# stm32hw02.net
KiCad netlist of a schematic drawn in EAGLE
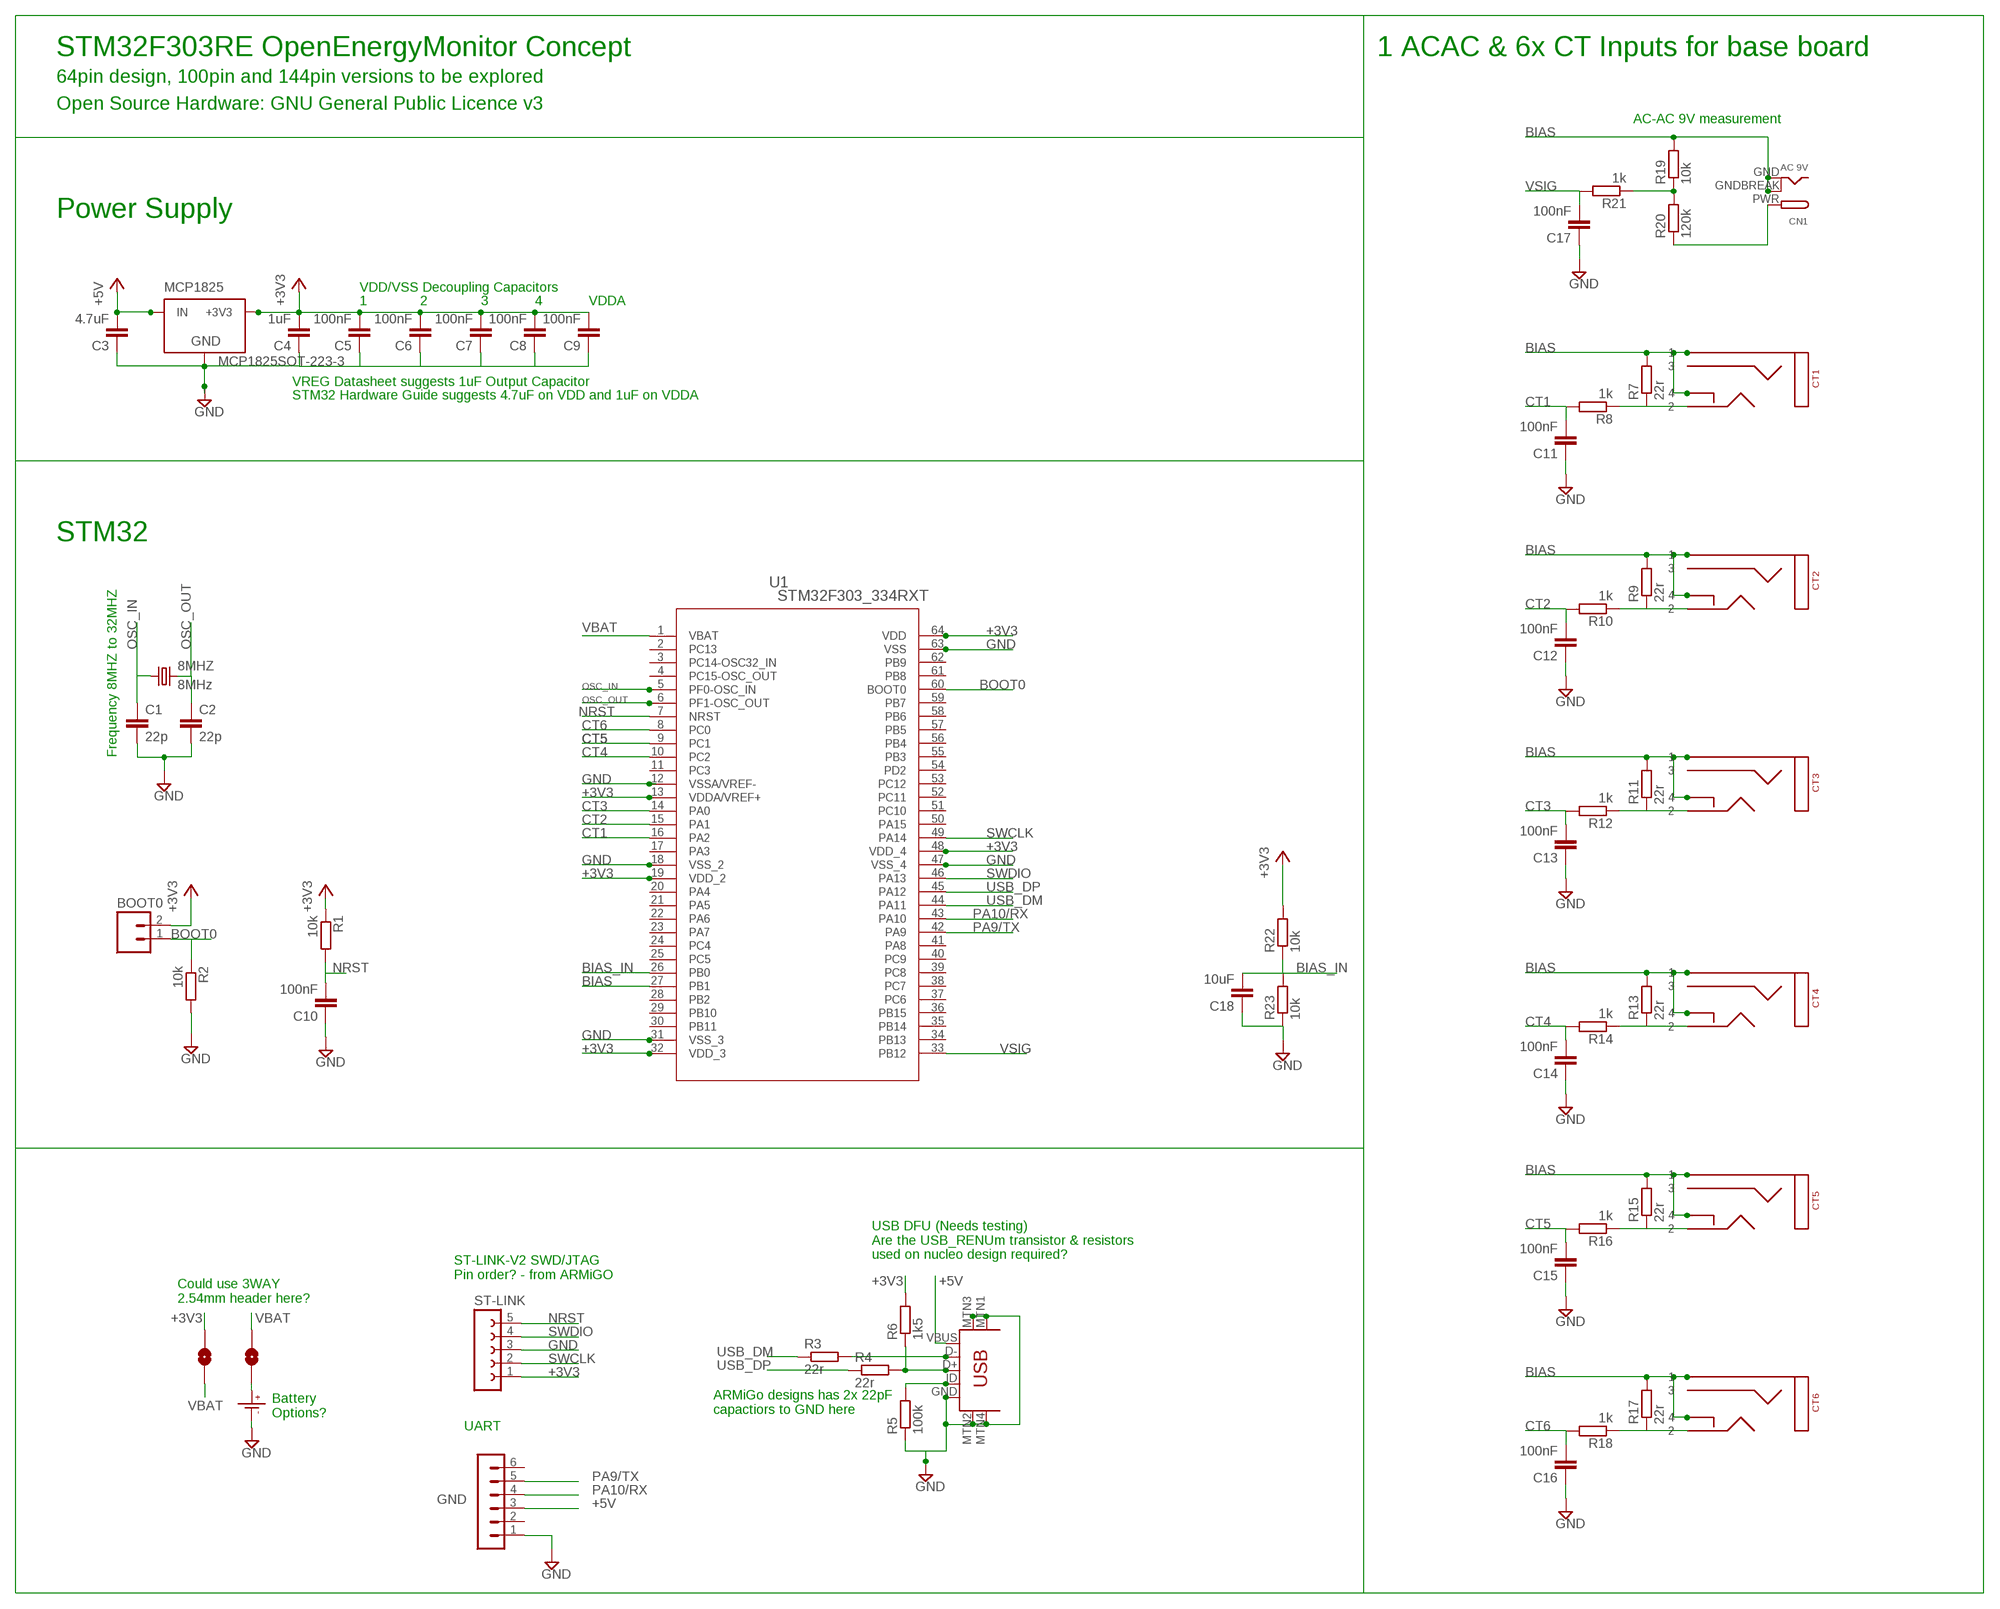
[diagram p0: schematic, sheet 1]

(export (version "E")
  (design (tool "Eeschema 10.0.6"))
  (components
    (comp (ref "3V3")
      (value "SOLDERJUMPERNO")
      (footprint "eagle-import:SJ_2S-NO")
      (libsource (lib "eagle-import") (part "SOLDERJUMPERNO"))
    )
    (comp (ref "8MHZ")
      (value "8MHz")
      (footprint "eagle-import:CRYSTAL-SMD-5X3")
      (libsource (lib "eagle-import") (part "CRYSTAL5X3"))
    )
    (comp (ref "BATTERY")
      (value "SOLDERJUMPERNO")
      (footprint "eagle-import:SJ_2S-NO")
      (libsource (lib "eagle-import") (part "SOLDERJUMPERNO"))
    )
    (comp (ref "BOOT0")
      (value "M02PTH")
      (footprint "eagle-import:1X02")
      (libsource (lib "eagle-import") (part "M02PTH"))
    )
    (comp (ref "C1")
      (value "22p")
      (footprint "eagle-import:C0603")
      (libsource (lib "eagle-import") (part "C-EUC0603"))
    )
    (comp (ref "C2")
      (value "22p")
      (footprint "eagle-import:C0603")
      (libsource (lib "eagle-import") (part "C-EUC0603"))
    )
    (comp (ref "C3")
      (value "4.7uF")
      (footprint "eagle-import:C0603")
      (libsource (lib "eagle-import") (part "C-EUC0603"))
    )
    (comp (ref "C4")
      (value "1uF")
      (footprint "eagle-import:C0603")
      (libsource (lib "eagle-import") (part "C-EUC0603"))
    )
    (comp (ref "C5")
      (value "100nF")
      (footprint "eagle-import:C0603")
      (libsource (lib "eagle-import") (part "C-EUC0603"))
    )
    (comp (ref "C6")
      (value "100nF")
      (footprint "eagle-import:C0603")
      (libsource (lib "eagle-import") (part "C-EUC0603"))
    )
    (comp (ref "C7")
      (value "100nF")
      (footprint "eagle-import:C0603")
      (libsource (lib "eagle-import") (part "C-EUC0603"))
    )
    (comp (ref "C8")
      (value "100nF")
      (footprint "eagle-import:C0603")
      (libsource (lib "eagle-import") (part "C-EUC0603"))
    )
    (comp (ref "C9")
      (value "100nF")
      (footprint "eagle-import:C0603")
      (libsource (lib "eagle-import") (part "C-EUC0603"))
    )
    (comp (ref "C10")
      (value "100nF")
      (footprint "eagle-import:C0603")
      (libsource (lib "eagle-import") (part "C-EUC0603"))
    )
    (comp (ref "C11")
      (value "100nF")
      (footprint "eagle-import:C0603")
      (libsource (lib "eagle-import") (part "C-EUC0603"))
    )
    (comp (ref "C12")
      (value "100nF")
      (footprint "eagle-import:C0603")
      (libsource (lib "eagle-import") (part "C-EUC0603"))
    )
    (comp (ref "C13")
      (value "100nF")
      (footprint "eagle-import:C0603")
      (libsource (lib "eagle-import") (part "C-EUC0603"))
    )
    (comp (ref "C14")
      (value "100nF")
      (footprint "eagle-import:C0603")
      (libsource (lib "eagle-import") (part "C-EUC0603"))
    )
    (comp (ref "C15")
      (value "100nF")
      (footprint "eagle-import:C0603")
      (libsource (lib "eagle-import") (part "C-EUC0603"))
    )
    (comp (ref "C16")
      (value "100nF")
      (footprint "eagle-import:C0603")
      (libsource (lib "eagle-import") (part "C-EUC0603"))
    )
    (comp (ref "C17")
      (value "100nF")
      (footprint "eagle-import:C0603")
      (libsource (lib "eagle-import") (part "C-EUC0603"))
    )
    (comp (ref "C18")
      (value "10uF")
      (footprint "eagle-import:C0603")
      (libsource (lib "eagle-import") (part "C-EUC0603"))
    )
    (comp (ref "CN1")
      (value "AC 9V")
      (footprint "eagle-import:DCJACK_2MM_PTH")
      (libsource (lib "eagle-import") (part "DCBARRELPTH"))
    )
    (comp (ref "CR1220")
      (value "CR1220SMD")
      (footprint "eagle-import:CR1220SMD")
      (fields (field (name "MPN") "Harwin S8411-45R"))
      (libsource (lib "eagle-import") (part "CR1220SMD"))
    )
    (comp (ref "CT1")
      (value "STEREO_SMD")
      (footprint "eagle-import:STEREO_SMT")
      (libsource (lib "eagle-import") (part "STEREO_SMD"))
    )
    (comp (ref "CT2")
      (value "STEREO_SMD")
      (footprint "eagle-import:STEREO_SMT")
      (libsource (lib "eagle-import") (part "STEREO_SMD"))
    )
    (comp (ref "CT3")
      (value "STEREO_SMD")
      (footprint "eagle-import:STEREO_SMT")
      (libsource (lib "eagle-import") (part "STEREO_SMD"))
    )
    (comp (ref "CT4")
      (value "STEREO_SMD")
      (footprint "eagle-import:STEREO_SMT")
      (libsource (lib "eagle-import") (part "STEREO_SMD"))
    )
    (comp (ref "CT5")
      (value "STEREO_SMD")
      (footprint "eagle-import:STEREO_SMT")
      (libsource (lib "eagle-import") (part "STEREO_SMD"))
    )
    (comp (ref "CT6")
      (value "STEREO_SMD")
      (footprint "eagle-import:STEREO_SMT")
      (libsource (lib "eagle-import") (part "STEREO_SMD"))
    )
    (comp (ref "GND")
      (value "UART")
      (footprint "eagle-import:MA06-1")
      (libsource (lib "eagle-import") (part "MA06-1"))
    )
    (comp (ref "MCP1825")
      (value "MCP1825SOT-223-3")
      (footprint "eagle-import:SOT-223")
      (libsource (lib "eagle-import") (part "MCP1825SOT-223-3"))
    )
    (comp (ref "R1")
      (value "10k")
      (footprint "eagle-import:R0603")
      (libsource (lib "eagle-import") (part "R-EU_R0603"))
    )
    (comp (ref "R2")
      (value "10k")
      (footprint "eagle-import:R0603")
      (libsource (lib "eagle-import") (part "R-EU_R0603"))
    )
    (comp (ref "R3")
      (value "22r")
      (footprint "eagle-import:R0603")
      (libsource (lib "eagle-import") (part "R-EU_R0603"))
    )
    (comp (ref "R4")
      (value "22r")
      (footprint "eagle-import:R0603")
      (libsource (lib "eagle-import") (part "R-EU_R0603"))
    )
    (comp (ref "R5")
      (value "100k")
      (footprint "eagle-import:R0603")
      (libsource (lib "eagle-import") (part "R-EU_R0603"))
    )
    (comp (ref "R6")
      (value "1k5")
      (footprint "eagle-import:R0603")
      (libsource (lib "eagle-import") (part "R-EU_R0603"))
    )
    (comp (ref "R7")
      (value "22r")
      (footprint "eagle-import:R0603")
      (libsource (lib "eagle-import") (part "R-EU_R0603"))
    )
    (comp (ref "R8")
      (value "1k")
      (footprint "eagle-import:R0603")
      (libsource (lib "eagle-import") (part "R-EU_R0603"))
    )
    (comp (ref "R9")
      (value "22r")
      (footprint "eagle-import:R0603")
      (libsource (lib "eagle-import") (part "R-EU_R0603"))
    )
    (comp (ref "R10")
      (value "1k")
      (footprint "eagle-import:R0603")
      (libsource (lib "eagle-import") (part "R-EU_R0603"))
    )
    (comp (ref "R11")
      (value "22r")
      (footprint "eagle-import:R0603")
      (libsource (lib "eagle-import") (part "R-EU_R0603"))
    )
    (comp (ref "R12")
      (value "1k")
      (footprint "eagle-import:R0603")
      (libsource (lib "eagle-import") (part "R-EU_R0603"))
    )
    (comp (ref "R13")
      (value "22r")
      (footprint "eagle-import:R0603")
      (libsource (lib "eagle-import") (part "R-EU_R0603"))
    )
    (comp (ref "R14")
      (value "1k")
      (footprint "eagle-import:R0603")
      (libsource (lib "eagle-import") (part "R-EU_R0603"))
    )
    (comp (ref "R15")
      (value "22r")
      (footprint "eagle-import:R0603")
      (libsource (lib "eagle-import") (part "R-EU_R0603"))
    )
    (comp (ref "R16")
      (value "1k")
      (footprint "eagle-import:R0603")
      (libsource (lib "eagle-import") (part "R-EU_R0603"))
    )
    (comp (ref "R17")
      (value "22r")
      (footprint "eagle-import:R0603")
      (libsource (lib "eagle-import") (part "R-EU_R0603"))
    )
    (comp (ref "R18")
      (value "1k")
      (footprint "eagle-import:R0603")
      (libsource (lib "eagle-import") (part "R-EU_R0603"))
    )
    (comp (ref "R19")
      (value "10k")
      (footprint "eagle-import:R0603")
      (libsource (lib "eagle-import") (part "R-EU_R0603"))
    )
    (comp (ref "R20")
      (value "120k")
      (footprint "eagle-import:R0603")
      (libsource (lib "eagle-import") (part "R-EU_R0603"))
    )
    (comp (ref "R21")
      (value "1k")
      (footprint "eagle-import:R0603")
      (libsource (lib "eagle-import") (part "R-EU_R0603"))
    )
    (comp (ref "R22")
      (value "10k")
      (footprint "eagle-import:R0603")
      (libsource (lib "eagle-import") (part "R-EU_R0603"))
    )
    (comp (ref "R23")
      (value "10k")
      (footprint "eagle-import:R0603")
      (libsource (lib "eagle-import") (part "R-EU_R0603"))
    )
    (comp (ref "ST-LINK")
      (value "FE05-1")
      (footprint "eagle-import:FE05-1")
      (libsource (lib "eagle-import") (part "FE05-1"))
    )
    (comp (ref "U$10")
      (value "USB-MINIB-5PIN")
      (footprint "eagle-import:USB-MINIB-CISECO")
      (libsource (lib "eagle-import") (part "USB-MINIB-5PIN"))
    )
    (comp (ref "U1")
      (value "STM32F303_334RXT")
      (footprint "eagle-import:LQFP64-10X10MM")
      (fields (field (name "MANUFACTURER_PART_NUMBER") "stm32f303_334rxt"))
      (libsource (lib "eagle-import") (part "STM32F303_334RXT"))
    )
  )
  (nets
    (net (code "1") (name "+3V3") (class "Default")
      (node (ref "3V3") (pin "1") (pinfunction "1_1") (pintype "passive"))
      (node (ref "BOOT0") (pin "2") (pinfunction "2_2") (pintype "passive"))
      (node (ref "C4") (pin "2") (pinfunction "2_2") (pintype "passive"))
      (node (ref "C5") (pin "2") (pinfunction "2_2") (pintype "passive"))
      (node (ref "C6") (pin "2") (pinfunction "2_2") (pintype "passive"))
      (node (ref "C7") (pin "2") (pinfunction "2_2") (pintype "passive"))
      (node (ref "C8") (pin "2") (pinfunction "2_2") (pintype "passive"))
      (node (ref "C9") (pin "2") (pinfunction "2_2") (pintype "passive"))
      (node (ref "MCP1825") (pin "3") (pinfunction "+3V3_3") (pintype "power_in"))
      (node (ref "R1") (pin "1") (pinfunction "1_1") (pintype "passive"))
      (node (ref "R22") (pin "2") (pinfunction "2_2") (pintype "passive"))
      (node (ref "R6") (pin "2") (pinfunction "2_2") (pintype "passive"))
      (node (ref "ST-LINK") (pin "1") (pinfunction "1_1") (pintype "passive"))
      (node (ref "U1") (pin "13") (pinfunction "VDDA/VREF+_13") (pintype "power_in"))
      (node (ref "U1") (pin "19") (pinfunction "VDD_2_19") (pintype "power_in"))
      (node (ref "U1") (pin "32") (pinfunction "VDD_3_32") (pintype "power_in"))
      (node (ref "U1") (pin "48") (pinfunction "VDD_4_48") (pintype "power_in"))
      (node (ref "U1") (pin "64") (pinfunction "VDD_64") (pintype "power_in"))
    )
    (net (code "2") (name "+5V") (class "Default")
      (node (ref "C3") (pin "2") (pinfunction "2_2") (pintype "passive"))
      (node (ref "GND") (pin "3") (pinfunction "3_3") (pintype "passive"))
      (node (ref "MCP1825") (pin "1") (pinfunction "IN_1") (pintype "power_in"))
      (node (ref "U$10") (pin "VBUS") (pinfunction "VBUS_VBUS") (pintype "bidirectional"))
    )
    (net (code "3") (name "/BIAS") (class "Default")
      (node (ref "CN1") (pin "GND") (pinfunction "GND_GND") (pintype "power_in"))
      (node (ref "CN1") (pin "GNDBREAK") (pinfunction "GNDBREAK_GNDBREAK") (pintype "power_in"))
      (node (ref "CT1") (pin "P$1") (pinfunction "1_P$1") (pintype "bidirectional"))
      (node (ref "CT1") (pin "P$4") (pinfunction "4_P$4") (pintype "bidirectional"))
      (node (ref "CT2") (pin "P$1") (pinfunction "1_P$1") (pintype "bidirectional"))
      (node (ref "CT2") (pin "P$4") (pinfunction "4_P$4") (pintype "bidirectional"))
      (node (ref "CT3") (pin "P$1") (pinfunction "1_P$1") (pintype "bidirectional"))
      (node (ref "CT3") (pin "P$4") (pinfunction "4_P$4") (pintype "bidirectional"))
      (node (ref "CT4") (pin "P$1") (pinfunction "1_P$1") (pintype "bidirectional"))
      (node (ref "CT4") (pin "P$4") (pinfunction "4_P$4") (pintype "bidirectional"))
      (node (ref "CT5") (pin "P$1") (pinfunction "1_P$1") (pintype "bidirectional"))
      (node (ref "CT5") (pin "P$4") (pinfunction "4_P$4") (pintype "bidirectional"))
      (node (ref "CT6") (pin "P$1") (pinfunction "1_P$1") (pintype "bidirectional"))
      (node (ref "CT6") (pin "P$4") (pinfunction "4_P$4") (pintype "bidirectional"))
      (node (ref "R11") (pin "2") (pinfunction "2_2") (pintype "passive"))
      (node (ref "R13") (pin "2") (pinfunction "2_2") (pintype "passive"))
      (node (ref "R15") (pin "2") (pinfunction "2_2") (pintype "passive"))
      (node (ref "R17") (pin "2") (pinfunction "2_2") (pintype "passive"))
      (node (ref "R19") (pin "2") (pinfunction "2_2") (pintype "passive"))
      (node (ref "R7") (pin "2") (pinfunction "2_2") (pintype "passive"))
      (node (ref "R9") (pin "2") (pinfunction "2_2") (pintype "passive"))
      (node (ref "U1") (pin "27") (pinfunction "PB1_27") (pintype "bidirectional"))
    )
    (net (code "4") (name "/BIAS_IN") (class "Default")
      (node (ref "C18") (pin "2") (pinfunction "2_2") (pintype "passive"))
      (node (ref "R22") (pin "1") (pinfunction "1_1") (pintype "passive"))
      (node (ref "R23") (pin "2") (pinfunction "2_2") (pintype "passive"))
      (node (ref "U1") (pin "26") (pinfunction "PB0_26") (pintype "bidirectional"))
    )
    (net (code "5") (name "/BOOT0") (class "Default")
      (node (ref "BOOT0") (pin "1") (pinfunction "1_1") (pintype "passive"))
      (node (ref "R2") (pin "1") (pinfunction "1_1") (pintype "passive"))
      (node (ref "U1") (pin "60") (pinfunction "BOOT0_60") (pintype "input"))
    )
    (net (code "6") (name "/CT1") (class "Default")
      (node (ref "C11") (pin "2") (pinfunction "2_2") (pintype "passive"))
      (node (ref "R8") (pin "2") (pinfunction "2_2") (pintype "passive"))
      (node (ref "U1") (pin "16") (pinfunction "PA2_16") (pintype "bidirectional"))
    )
    (net (code "7") (name "/CT2") (class "Default")
      (node (ref "C12") (pin "2") (pinfunction "2_2") (pintype "passive"))
      (node (ref "R10") (pin "2") (pinfunction "2_2") (pintype "passive"))
      (node (ref "U1") (pin "15") (pinfunction "PA1_15") (pintype "bidirectional"))
    )
    (net (code "8") (name "/CT3") (class "Default")
      (node (ref "C13") (pin "2") (pinfunction "2_2") (pintype "passive"))
      (node (ref "R12") (pin "2") (pinfunction "2_2") (pintype "passive"))
      (node (ref "U1") (pin "14") (pinfunction "PA0_14") (pintype "bidirectional"))
    )
    (net (code "9") (name "/CT4") (class "Default")
      (node (ref "C14") (pin "2") (pinfunction "2_2") (pintype "passive"))
      (node (ref "R14") (pin "2") (pinfunction "2_2") (pintype "passive"))
      (node (ref "U1") (pin "10") (pinfunction "PC2_10") (pintype "bidirectional"))
    )
    (net (code "10") (name "/CT5") (class "Default")
      (node (ref "C15") (pin "2") (pinfunction "2_2") (pintype "passive"))
      (node (ref "R16") (pin "2") (pinfunction "2_2") (pintype "passive"))
      (node (ref "U1") (pin "9") (pinfunction "PC1_9") (pintype "bidirectional"))
    )
    (net (code "11") (name "/CT6") (class "Default")
      (node (ref "C16") (pin "2") (pinfunction "2_2") (pintype "passive"))
      (node (ref "R18") (pin "2") (pinfunction "2_2") (pintype "passive"))
      (node (ref "U1") (pin "8") (pinfunction "PC0_8") (pintype "bidirectional"))
    )
    (net (code "12") (name "/NRST") (class "Default")
      (node (ref "C10") (pin "2") (pinfunction "2_2") (pintype "passive"))
      (node (ref "R1") (pin "2") (pinfunction "2_2") (pintype "passive"))
      (node (ref "ST-LINK") (pin "5") (pinfunction "5_5") (pintype "passive"))
      (node (ref "U1") (pin "7") (pinfunction "NRST_7") (pintype "bidirectional"))
    )
    (net (code "13") (name "/OSC_IN") (class "Default")
      (node (ref "8MHZ") (pin "1") (pinfunction "1_1") (pintype "passive"))
      (node (ref "C1") (pin "1") (pinfunction "1_1") (pintype "passive"))
      (node (ref "U1") (pin "5") (pinfunction "PF0-OSC_IN_5") (pintype "bidirectional"))
    )
    (net (code "14") (name "/OSC_OUT") (class "Default")
      (node (ref "8MHZ") (pin "3") (pinfunction "2_3") (pintype "passive"))
      (node (ref "C2") (pin "1") (pinfunction "1_1") (pintype "passive"))
      (node (ref "U1") (pin "6") (pinfunction "PF1-OSC_OUT_6") (pintype "bidirectional"))
    )
    (net (code "15") (name "/PA9{slash}TX") (class "Default")
      (node (ref "GND") (pin "5") (pinfunction "5_5") (pintype "passive"))
      (node (ref "U1") (pin "42") (pinfunction "PA9_42") (pintype "bidirectional"))
    )
    (net (code "16") (name "/PA10{slash}RX") (class "Default")
      (node (ref "GND") (pin "4") (pinfunction "4_4") (pintype "passive"))
      (node (ref "U1") (pin "43") (pinfunction "PA10_43") (pintype "bidirectional"))
    )
    (net (code "17") (name "/SWCLK") (class "Default")
      (node (ref "ST-LINK") (pin "2") (pinfunction "2_2") (pintype "passive"))
      (node (ref "U1") (pin "49") (pinfunction "PA14_49") (pintype "bidirectional"))
    )
    (net (code "18") (name "/SWDIO") (class "Default")
      (node (ref "ST-LINK") (pin "4") (pinfunction "4_4") (pintype "passive"))
      (node (ref "U1") (pin "46") (pinfunction "PA13_46") (pintype "bidirectional"))
    )
    (net (code "19") (name "/USB_DM") (class "Default")
      (node (ref "R3") (pin "1") (pinfunction "1_1") (pintype "passive"))
      (node (ref "U1") (pin "44") (pinfunction "PA11_44") (pintype "bidirectional"))
    )
    (net (code "20") (name "/USB_DP") (class "Default")
      (node (ref "R4") (pin "1") (pinfunction "1_1") (pintype "passive"))
      (node (ref "U1") (pin "45") (pinfunction "PA12_45") (pintype "bidirectional"))
    )
    (net (code "21") (name "/VBAT") (class "Default")
      (node (ref "3V3") (pin "2") (pinfunction "2_2") (pintype "passive"))
      (node (ref "BATTERY") (pin "1") (pinfunction "1_1") (pintype "passive"))
      (node (ref "U1") (pin "1") (pinfunction "VBAT_1") (pintype "power_in"))
    )
    (net (code "22") (name "/VSIG") (class "Default")
      (node (ref "C17") (pin "2") (pinfunction "2_2") (pintype "passive"))
      (node (ref "R21") (pin "2") (pinfunction "2_2") (pintype "passive"))
      (node (ref "U1") (pin "33") (pinfunction "PB12_33") (pintype "bidirectional"))
    )
    (net (code "23") (name "GND") (class "Default")
      (node (ref "C1") (pin "2") (pinfunction "2_2") (pintype "passive"))
      (node (ref "C10") (pin "1") (pinfunction "1_1") (pintype "passive"))
      (node (ref "C11") (pin "1") (pinfunction "1_1") (pintype "passive"))
      (node (ref "C12") (pin "1") (pinfunction "1_1") (pintype "passive"))
      (node (ref "C13") (pin "1") (pinfunction "1_1") (pintype "passive"))
      (node (ref "C14") (pin "1") (pinfunction "1_1") (pintype "passive"))
      (node (ref "C15") (pin "1") (pinfunction "1_1") (pintype "passive"))
      (node (ref "C16") (pin "1") (pinfunction "1_1") (pintype "passive"))
      (node (ref "C17") (pin "1") (pinfunction "1_1") (pintype "passive"))
      (node (ref "C18") (pin "1") (pinfunction "1_1") (pintype "passive"))
      (node (ref "C2") (pin "2") (pinfunction "2_2") (pintype "passive"))
      (node (ref "C3") (pin "1") (pinfunction "1_1") (pintype "passive"))
      (node (ref "C4") (pin "1") (pinfunction "1_1") (pintype "passive"))
      (node (ref "C5") (pin "1") (pinfunction "1_1") (pintype "passive"))
      (node (ref "C6") (pin "1") (pinfunction "1_1") (pintype "passive"))
      (node (ref "C7") (pin "1") (pinfunction "1_1") (pintype "passive"))
      (node (ref "C8") (pin "1") (pinfunction "1_1") (pintype "passive"))
      (node (ref "C9") (pin "1") (pinfunction "1_1") (pintype "passive"))
      (node (ref "CR1220") (pin "P-") (pinfunction "P$-_P-") (pintype "bidirectional"))
      (node (ref "GND") (pin "1") (pinfunction "1_1") (pintype "passive"))
      (node (ref "MCP1825") (pin "2") (pinfunction "GND_2") (pintype "power_in"))
      (node (ref "R2") (pin "2") (pinfunction "2_2") (pintype "passive"))
      (node (ref "R23") (pin "1") (pinfunction "1_1") (pintype "passive"))
      (node (ref "R5") (pin "1") (pinfunction "1_1") (pintype "passive"))
      (node (ref "ST-LINK") (pin "3") (pinfunction "3_3") (pintype "passive"))
      (node (ref "U$10") (pin "GND") (pinfunction "GND_GND") (pintype "bidirectional"))
      (node (ref "U$10") (pin "MTN1") (pinfunction "MTN2_MTN1") (pintype "bidirectional"))
      (node (ref "U$10") (pin "MTN2") (pinfunction "MTN3_MTN2") (pintype "bidirectional"))
      (node (ref "U$10") (pin "MTN3") (pinfunction "MTN1_MTN3") (pintype "bidirectional"))
      (node (ref "U$10") (pin "MTN4") (pinfunction "MTN4_MTN4") (pintype "bidirectional"))
      (node (ref "U1") (pin "12") (pinfunction "VSSA/VREF-_12") (pintype "power_in"))
      (node (ref "U1") (pin "18") (pinfunction "VSS_2_18") (pintype "power_in"))
      (node (ref "U1") (pin "31") (pinfunction "VSS_3_31") (pintype "power_in"))
      (node (ref "U1") (pin "47") (pinfunction "VSS_4_47") (pintype "power_in"))
      (node (ref "U1") (pin "63") (pinfunction "VSS_63") (pintype "power_in"))
    )
    (net (code "24") (name "Net-(CN1-PadPWR)") (class "Default")
      (node (ref "CN1") (pin "PWR") (pinfunction "PWR_PWR") (pintype "power_in"))
      (node (ref "R20") (pin "1") (pinfunction "1_1") (pintype "passive"))
    )
    (net (code "25") (name "Net-(CR1220-P$+)") (class "Default")
      (node (ref "BATTERY") (pin "2") (pinfunction "2_2") (pintype "passive"))
      (node (ref "CR1220") (pin "P+") (pinfunction "P$+_P+") (pintype "bidirectional"))
    )
    (net (code "26") (name "Net-(CT1-2)") (class "Default")
      (node (ref "CT1") (pin "P$2") (pinfunction "2_P$2") (pintype "bidirectional"))
      (node (ref "R7") (pin "1") (pinfunction "1_1") (pintype "passive"))
      (node (ref "R8") (pin "1") (pinfunction "1_1") (pintype "passive"))
    )
    (net (code "27") (name "Net-(CT2-2)") (class "Default")
      (node (ref "CT2") (pin "P$2") (pinfunction "2_P$2") (pintype "bidirectional"))
      (node (ref "R10") (pin "1") (pinfunction "1_1") (pintype "passive"))
      (node (ref "R9") (pin "1") (pinfunction "1_1") (pintype "passive"))
    )
    (net (code "28") (name "Net-(CT3-2)") (class "Default")
      (node (ref "CT3") (pin "P$2") (pinfunction "2_P$2") (pintype "bidirectional"))
      (node (ref "R11") (pin "1") (pinfunction "1_1") (pintype "passive"))
      (node (ref "R12") (pin "1") (pinfunction "1_1") (pintype "passive"))
    )
    (net (code "29") (name "Net-(CT4-2)") (class "Default")
      (node (ref "CT4") (pin "P$2") (pinfunction "2_P$2") (pintype "bidirectional"))
      (node (ref "R13") (pin "1") (pinfunction "1_1") (pintype "passive"))
      (node (ref "R14") (pin "1") (pinfunction "1_1") (pintype "passive"))
    )
    (net (code "30") (name "Net-(CT5-2)") (class "Default")
      (node (ref "CT5") (pin "P$2") (pinfunction "2_P$2") (pintype "bidirectional"))
      (node (ref "R15") (pin "1") (pinfunction "1_1") (pintype "passive"))
      (node (ref "R16") (pin "1") (pinfunction "1_1") (pintype "passive"))
    )
    (net (code "31") (name "Net-(CT6-2)") (class "Default")
      (node (ref "CT6") (pin "P$2") (pinfunction "2_P$2") (pintype "bidirectional"))
      (node (ref "R17") (pin "1") (pinfunction "1_1") (pintype "passive"))
      (node (ref "R18") (pin "1") (pinfunction "1_1") (pintype "passive"))
    )
    (net (code "32") (name "Net-(R3-Pad2)") (class "Default")
      (node (ref "R3") (pin "2") (pinfunction "2_2") (pintype "passive"))
      (node (ref "U$10") (pin "D-") (pinfunction "D-_D-") (pintype "bidirectional"))
    )
    (net (code "33") (name "Net-(R4-Pad2)") (class "Default")
      (node (ref "R4") (pin "2") (pinfunction "2_2") (pintype "passive"))
      (node (ref "R6") (pin "1") (pinfunction "1_1") (pintype "passive"))
      (node (ref "U$10") (pin "D+") (pinfunction "D+_D+") (pintype "bidirectional"))
    )
    (net (code "34") (name "Net-(R5-Pad2)") (class "Default")
      (node (ref "R5") (pin "2") (pinfunction "2_2") (pintype "passive"))
      (node (ref "U$10") (pin "ID") (pinfunction "ID_ID") (pintype "bidirectional"))
    )
    (net (code "35") (name "Net-(R19-Pad1)") (class "Default")
      (node (ref "R19") (pin "1") (pinfunction "1_1") (pintype "passive"))
      (node (ref "R20") (pin "2") (pinfunction "2_2") (pintype "passive"))
      (node (ref "R21") (pin "1") (pinfunction "1_1") (pintype "passive"))
    )
    (net (code "36") (name "unconnected-(CT1-3-PadP$3)") (class "Default")
      (node (ref "CT1") (pin "P$3") (pinfunction "3_P$3") (pintype "bidirectional"))
    )
    (net (code "37") (name "unconnected-(CT2-3-PadP$3)") (class "Default")
      (node (ref "CT2") (pin "P$3") (pinfunction "3_P$3") (pintype "bidirectional"))
    )
    (net (code "38") (name "unconnected-(CT3-3-PadP$3)") (class "Default")
      (node (ref "CT3") (pin "P$3") (pinfunction "3_P$3") (pintype "bidirectional"))
    )
    (net (code "39") (name "unconnected-(CT4-3-PadP$3)") (class "Default")
      (node (ref "CT4") (pin "P$3") (pinfunction "3_P$3") (pintype "bidirectional"))
    )
    (net (code "40") (name "unconnected-(CT5-3-PadP$3)") (class "Default")
      (node (ref "CT5") (pin "P$3") (pinfunction "3_P$3") (pintype "bidirectional"))
    )
    (net (code "41") (name "unconnected-(CT6-3-PadP$3)") (class "Default")
      (node (ref "CT6") (pin "P$3") (pinfunction "3_P$3") (pintype "bidirectional"))
    )
    (net (code "42") (name "unconnected-(GND-Pad2)") (class "Default")
      (node (ref "GND") (pin "2") (pinfunction "2_2") (pintype "passive"))
    )
    (net (code "43") (name "unconnected-(GND-Pad6)") (class "Default")
      (node (ref "GND") (pin "6") (pinfunction "6_6") (pintype "passive"))
    )
    (net (code "44") (name "unconnected-(U1-PA3-Pad17)") (class "Default")
      (node (ref "U1") (pin "17") (pinfunction "PA3_17") (pintype "bidirectional"))
    )
    (net (code "45") (name "unconnected-(U1-PA4-Pad20)") (class "Default")
      (node (ref "U1") (pin "20") (pinfunction "PA4_20") (pintype "bidirectional"))
    )
    (net (code "46") (name "unconnected-(U1-PA5-Pad21)") (class "Default")
      (node (ref "U1") (pin "21") (pinfunction "PA5_21") (pintype "bidirectional"))
    )
    (net (code "47") (name "unconnected-(U1-PA6-Pad22)") (class "Default")
      (node (ref "U1") (pin "22") (pinfunction "PA6_22") (pintype "bidirectional"))
    )
    (net (code "48") (name "unconnected-(U1-PA7-Pad23)") (class "Default")
      (node (ref "U1") (pin "23") (pinfunction "PA7_23") (pintype "bidirectional"))
    )
    (net (code "49") (name "unconnected-(U1-PA8-Pad41)") (class "Default")
      (node (ref "U1") (pin "41") (pinfunction "PA8_41") (pintype "bidirectional"))
    )
    (net (code "50") (name "unconnected-(U1-PA15-Pad50)") (class "Default")
      (node (ref "U1") (pin "50") (pinfunction "PA15_50") (pintype "bidirectional"))
    )
    (net (code "51") (name "unconnected-(U1-PB2-Pad28)") (class "Default")
      (node (ref "U1") (pin "28") (pinfunction "PB2_28") (pintype "bidirectional"))
    )
    (net (code "52") (name "unconnected-(U1-PB3-Pad55)") (class "Default")
      (node (ref "U1") (pin "55") (pinfunction "PB3_55") (pintype "bidirectional"))
    )
    (net (code "53") (name "unconnected-(U1-PB4-Pad56)") (class "Default")
      (node (ref "U1") (pin "56") (pinfunction "PB4_56") (pintype "bidirectional"))
    )
    (net (code "54") (name "unconnected-(U1-PB5-Pad57)") (class "Default")
      (node (ref "U1") (pin "57") (pinfunction "PB5_57") (pintype "bidirectional"))
    )
    (net (code "55") (name "unconnected-(U1-PB6-Pad58)") (class "Default")
      (node (ref "U1") (pin "58") (pinfunction "PB6_58") (pintype "bidirectional"))
    )
    (net (code "56") (name "unconnected-(U1-PB7-Pad59)") (class "Default")
      (node (ref "U1") (pin "59") (pinfunction "PB7_59") (pintype "bidirectional"))
    )
    (net (code "57") (name "unconnected-(U1-PB8-Pad61)") (class "Default")
      (node (ref "U1") (pin "61") (pinfunction "PB8_61") (pintype "bidirectional"))
    )
    (net (code "58") (name "unconnected-(U1-PB9-Pad62)") (class "Default")
      (node (ref "U1") (pin "62") (pinfunction "PB9_62") (pintype "bidirectional"))
    )
    (net (code "59") (name "unconnected-(U1-PB10-Pad29)") (class "Default")
      (node (ref "U1") (pin "29") (pinfunction "PB10_29") (pintype "bidirectional"))
    )
    (net (code "60") (name "unconnected-(U1-PB11-Pad30)") (class "Default")
      (node (ref "U1") (pin "30") (pinfunction "PB11_30") (pintype "bidirectional"))
    )
    (net (code "61") (name "unconnected-(U1-PB13-Pad34)") (class "Default")
      (node (ref "U1") (pin "34") (pinfunction "PB13_34") (pintype "bidirectional"))
    )
    (net (code "62") (name "unconnected-(U1-PB14-Pad35)") (class "Default")
      (node (ref "U1") (pin "35") (pinfunction "PB14_35") (pintype "bidirectional"))
    )
    (net (code "63") (name "unconnected-(U1-PB15-Pad36)") (class "Default")
      (node (ref "U1") (pin "36") (pinfunction "PB15_36") (pintype "bidirectional"))
    )
    (net (code "64") (name "unconnected-(U1-PC3-Pad11)") (class "Default")
      (node (ref "U1") (pin "11") (pinfunction "PC3_11") (pintype "bidirectional"))
    )
    (net (code "65") (name "unconnected-(U1-PC4-Pad24)") (class "Default")
      (node (ref "U1") (pin "24") (pinfunction "PC4_24") (pintype "bidirectional"))
    )
    (net (code "66") (name "unconnected-(U1-PC5-Pad25)") (class "Default")
      (node (ref "U1") (pin "25") (pinfunction "PC5_25") (pintype "bidirectional"))
    )
    (net (code "67") (name "unconnected-(U1-PC6-Pad37)") (class "Default")
      (node (ref "U1") (pin "37") (pinfunction "PC6_37") (pintype "bidirectional"))
    )
    (net (code "68") (name "unconnected-(U1-PC7-Pad38)") (class "Default")
      (node (ref "U1") (pin "38") (pinfunction "PC7_38") (pintype "bidirectional"))
    )
    (net (code "69") (name "unconnected-(U1-PC8-Pad39)") (class "Default")
      (node (ref "U1") (pin "39") (pinfunction "PC8_39") (pintype "bidirectional"))
    )
    (net (code "70") (name "unconnected-(U1-PC9-Pad40)") (class "Default")
      (node (ref "U1") (pin "40") (pinfunction "PC9_40") (pintype "bidirectional"))
    )
    (net (code "71") (name "unconnected-(U1-PC10-Pad51)") (class "Default")
      (node (ref "U1") (pin "51") (pinfunction "PC10_51") (pintype "bidirectional"))
    )
    (net (code "72") (name "unconnected-(U1-PC11-Pad52)") (class "Default")
      (node (ref "U1") (pin "52") (pinfunction "PC11_52") (pintype "bidirectional"))
    )
    (net (code "73") (name "unconnected-(U1-PC12-Pad53)") (class "Default")
      (node (ref "U1") (pin "53") (pinfunction "PC12_53") (pintype "bidirectional"))
    )
    (net (code "74") (name "unconnected-(U1-PC13-Pad2)") (class "Default")
      (node (ref "U1") (pin "2") (pinfunction "PC13_2") (pintype "bidirectional"))
    )
    (net (code "75") (name "unconnected-(U1-PC14-OSC32_IN-Pad3)") (class "Default")
      (node (ref "U1") (pin "3") (pinfunction "PC14-OSC32_IN_3") (pintype "bidirectional"))
    )
    (net (code "76") (name "unconnected-(U1-PC15-OSC_OUT-Pad4)") (class "Default")
      (node (ref "U1") (pin "4") (pinfunction "PC15-OSC_OUT_4") (pintype "bidirectional"))
    )
    (net (code "77") (name "unconnected-(U1-PD2-Pad54)") (class "Default")
      (node (ref "U1") (pin "54") (pinfunction "PD2_54") (pintype "bidirectional"))
    )
  )
)
